# photodiodeAmplifier.net
KiCad netlist of a schematic drawn in Altium Designer
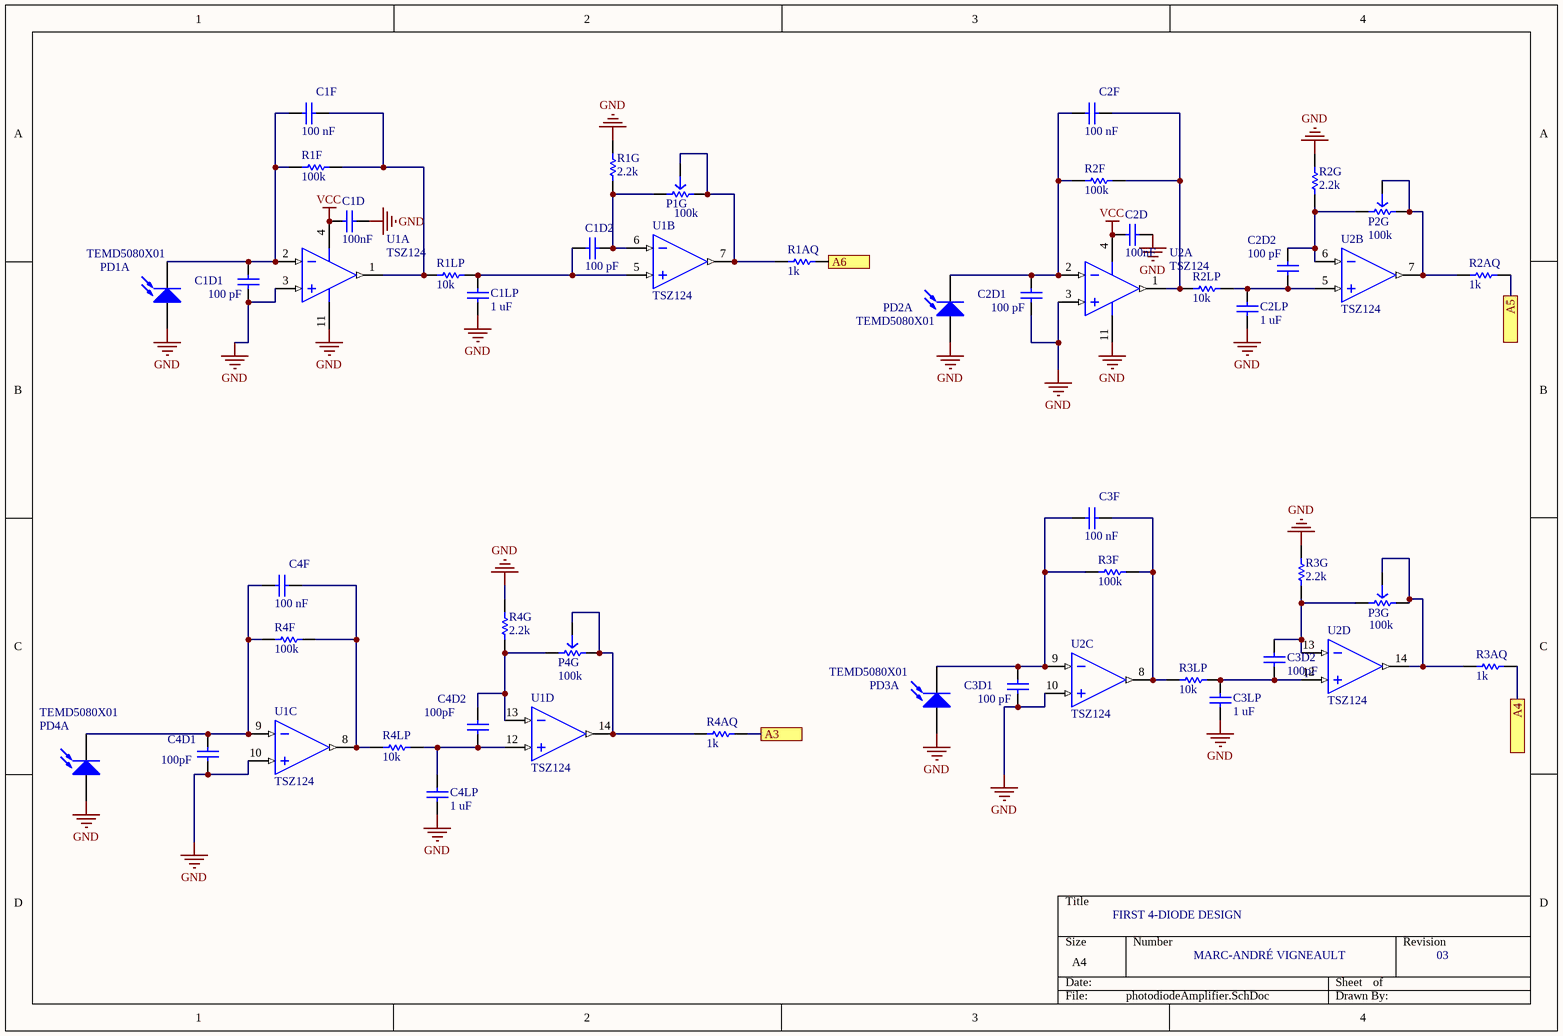
[diagram p0: photodiodeAmplifier.SchDoc]

(export (version "E")
  (design (tool "Eeschema 10.0.6"))
  (components
    (comp (ref "C1D") (value "100nF") (footprint "CAP 0805") (libsource (lib "AcqBoxLib") (part "CAP 0805")))
    (comp (ref "C1D1")
      (value "100 pF")
      (footprint "CAP 0805")
      (libsource (lib "AcqBoxLib") (part "CAP 0805"))
    )
    (comp (ref "C1D2")
      (value "100 pF")
      (footprint "CAP 0805")
      (libsource (lib "AcqBoxLib") (part "CAP 0805"))
    )
    (comp (ref "C1F") (value "100 nF") (footprint "CAP 0805") (libsource (lib "AcqBoxLib") (part "CAP 0805")))
    (comp (ref "C1LP") (value "1 uF") (footprint "CAP 0805") (libsource (lib "AcqBoxLib") (part "CAP 0805")))
    (comp (ref "C2D") (value "100nF") (footprint "CAP 0805") (libsource (lib "AcqBoxLib") (part "CAP 0805")))
    (comp (ref "C2D1")
      (value "100 pF")
      (footprint "CAP 0805")
      (libsource (lib "AcqBoxLib") (part "CAP 0805"))
    )
    (comp (ref "C2D2")
      (value "100 pF")
      (footprint "CAP 0805")
      (libsource (lib "AcqBoxLib") (part "CAP 0805"))
    )
    (comp (ref "C2F") (value "100 nF") (footprint "CAP 0805") (libsource (lib "AcqBoxLib") (part "CAP 0805")))
    (comp (ref "C2LP") (value "1 uF") (footprint "CAP 0805") (libsource (lib "AcqBoxLib") (part "CAP 0805")))
    (comp (ref "C3D1")
      (value "100 pF")
      (footprint "CAP 0805")
      (libsource (lib "AcqBoxLib") (part "CAP 0805"))
    )
    (comp (ref "C3D2") (value "100pF") (footprint "CAP 0805") (libsource (lib "AcqBoxLib") (part "CAP 0805")))
    (comp (ref "C3F") (value "100 nF") (footprint "CAP 0805") (libsource (lib "AcqBoxLib") (part "CAP 0805")))
    (comp (ref "C3LP") (value "1 uF") (footprint "CAP 0805") (libsource (lib "AcqBoxLib") (part "CAP 0805")))
    (comp (ref "C4D1") (value "100pF") (footprint "CAP 0805") (libsource (lib "AcqBoxLib") (part "CAP 0805")))
    (comp (ref "C4D2") (value "100pF") (footprint "CAP 0805") (libsource (lib "AcqBoxLib") (part "CAP 0805")))
    (comp (ref "C4F") (value "100 nF") (footprint "CAP 0805") (libsource (lib "AcqBoxLib") (part "CAP 0805")))
    (comp (ref "C4LP") (value "1 uF") (footprint "CAP 0805") (libsource (lib "AcqBoxLib") (part "CAP 0805")))
    (comp (ref "P1G")
      (value "100k")
      (footprint "potentiometer trimmer straight")
      (libsource (lib "AcqBoxLib") (part "Potentiometer Trimmer 90deg"))
    )
    (comp (ref "P2G")
      (value "100k")
      (footprint "potentiometer trimmer straight")
      (fields (field (name "Comment") "Potentiometer Trimmer 90deg"))
      (libsource (lib "AcqBoxLib") (part "Potentiometer Trimmer 90deg"))
    )
    (comp (ref "P3G")
      (value "100k")
      (footprint "potentiometer trimmer straight")
      (fields (field (name "Comment") "Potentiometer Trimmer 90deg"))
      (libsource (lib "AcqBoxLib") (part "Potentiometer Trimmer 90deg"))
    )
    (comp (ref "P4G")
      (value "100k")
      (footprint "potentiometer trimmer straight")
      (libsource (lib "AcqBoxLib") (part "Potentiometer Trimmer 90deg"))
    )
    (comp (ref "PD1")
      (value "TEMD5080X01")
      (footprint "Photodiode SMD PKG-1")
      (description "PIN Sillicium photodiode.")
      (libsource (lib "neigeMegaShieldLibrary") (part "TEMD5080X01"))
    )
    (comp (ref "PD2")
      (value "TEMD5080X01")
      (footprint "Photodiode SMD PKG-1")
      (description "PIN Sillicium photodiode.")
      (libsource (lib "neigeMegaShieldLibrary") (part "TEMD5080X01"))
    )
    (comp (ref "PD3")
      (value "TEMD5080X01")
      (footprint "Photodiode SMD PKG-1")
      (description "PIN Sillicium photodiode.")
      (libsource (lib "neigeMegaShieldLibrary") (part "TEMD5080X01"))
    )
    (comp (ref "PD4")
      (value "TEMD5080X01")
      (footprint "Photodiode SMD PKG-1")
      (description "PIN Sillicium photodiode.")
      (libsource (lib "neigeMegaShieldLibrary") (part "TEMD5080X01"))
    )
    (comp (ref "R1AQ")
      (value "1k")
      (footprint "RES 0805")
      (description "SMD Resistor 0805")
      (fields (field (name "Comment") "RES 0805"))
      (libsource (lib "AcqBoxLib") (part "RES 0805"))
    )
    (comp (ref "R1F")
      (value "100k")
      (footprint "RES 0805")
      (description "SMD Resistor 0805")
      (fields (field (name "Comment") "RES 0805"))
      (libsource (lib "AcqBoxLib") (part "RES 0805"))
    )
    (comp (ref "R1G")
      (value "2.2k")
      (footprint "RES 0805")
      (description "SMD Resistor 0805")
      (fields (field (name "Comment") "RES 0805"))
      (libsource (lib "AcqBoxLib") (part "RES 0805"))
    )
    (comp (ref "R1LP")
      (value "10k")
      (footprint "RES 0805")
      (description "SMD Resistor 0805")
      (fields (field (name "Comment") "RES 0805"))
      (libsource (lib "AcqBoxLib") (part "RES 0805"))
    )
    (comp (ref "R2AQ")
      (value "1k")
      (footprint "RES 0805")
      (description "SMD Resistor 0805")
      (fields (field (name "Comment") "RES 0805"))
      (libsource (lib "AcqBoxLib") (part "RES 0805"))
    )
    (comp (ref "R2F")
      (value "100k")
      (footprint "RES 0805")
      (description "SMD Resistor 0805")
      (fields (field (name "Comment") "RES 0805"))
      (libsource (lib "AcqBoxLib") (part "RES 0805"))
    )
    (comp (ref "R2G")
      (value "2.2k")
      (footprint "RES 0805")
      (description "SMD Resistor 0805")
      (fields (field (name "Comment") "RES 0805"))
      (libsource (lib "AcqBoxLib") (part "RES 0805"))
    )
    (comp (ref "R2LP")
      (value "10k")
      (footprint "RES 0805")
      (description "SMD Resistor 0805")
      (fields (field (name "Comment") "RES 0805"))
      (libsource (lib "AcqBoxLib") (part "RES 0805"))
    )
    (comp (ref "R3AQ")
      (value "1k")
      (footprint "RES 0805")
      (description "SMD Resistor 0805")
      (fields (field (name "Comment") "RES 0805"))
      (libsource (lib "AcqBoxLib") (part "RES 0805"))
    )
    (comp (ref "R3F")
      (value "100k")
      (footprint "RES 0805")
      (description "SMD Resistor 0805")
      (fields (field (name "Comment") "RES 0805"))
      (libsource (lib "AcqBoxLib") (part "RES 0805"))
    )
    (comp (ref "R3G")
      (value "2.2k")
      (footprint "RES 0805")
      (description "SMD Resistor 0805")
      (fields (field (name "Comment") "RES 0805"))
      (libsource (lib "AcqBoxLib") (part "RES 0805"))
    )
    (comp (ref "R3LP")
      (value "10k")
      (footprint "RES 0805")
      (description "SMD Resistor 0805")
      (fields (field (name "Comment") "RES 0805"))
      (libsource (lib "AcqBoxLib") (part "RES 0805"))
    )
    (comp (ref "R4AQ")
      (value "1k")
      (footprint "RES 0805")
      (description "SMD Resistor 0805")
      (fields (field (name "Comment") "RES 0805"))
      (libsource (lib "AcqBoxLib") (part "RES 0805"))
    )
    (comp (ref "R4F")
      (value "100k")
      (footprint "RES 0805")
      (description "SMD Resistor 0805")
      (fields (field (name "Comment") "RES 0805"))
      (libsource (lib "AcqBoxLib") (part "RES 0805"))
    )
    (comp (ref "R4G")
      (value "2.2k")
      (footprint "RES 0805")
      (description "SMD Resistor 0805")
      (fields (field (name "Comment") "RES 0805"))
      (libsource (lib "AcqBoxLib") (part "RES 0805"))
    )
    (comp (ref "R4LP")
      (value "10k")
      (footprint "RES 0805")
      (description "SMD Resistor 0805")
      (fields (field (name "Comment") "RES 0805"))
      (libsource (lib "AcqBoxLib") (part "RES 0805"))
    )
    (comp (ref "U1") (value "TSZ124") (footprint "TSSOP14") (libsource (lib "AcqBoxLib") (part "TSZ124")))
    (comp (ref "U2") (value "TSZ124") (footprint "TSSOP14") (libsource (lib "AcqBoxLib") (part "TSZ124")))
  )
  (nets
    (net (code "1") (name "/A3") (class "Default")
      (node (ref "R4AQ") (pin "2") (pinfunction "2_2") (pintype "passive"))
    )
    (net (code "2") (name "/A4") (class "Default")
      (node (ref "R3AQ") (pin "2") (pinfunction "2_2") (pintype "passive"))
    )
    (net (code "3") (name "/A5") (class "Default")
      (node (ref "R2AQ") (pin "2") (pinfunction "2_2") (pintype "passive"))
    )
    (net (code "4") (name "/A6") (class "Default")
      (node (ref "R1AQ") (pin "2") (pinfunction "2_2") (pintype "passive"))
    )
    (net (code "5") (name "GND") (class "Default")
      (node (ref "C1D") (pin "1") (pinfunction "1_1") (pintype "passive"))
      (node (ref "C1D1") (pin "1") (pinfunction "1_1") (pintype "passive"))
      (node (ref "C1LP") (pin "1") (pinfunction "1_1") (pintype "passive"))
      (node (ref "C2D") (pin "1") (pinfunction "1_1") (pintype "passive"))
      (node (ref "C2D1") (pin "1") (pinfunction "1_1") (pintype "passive"))
      (node (ref "C2LP") (pin "1") (pinfunction "1_1") (pintype "passive"))
      (node (ref "C3D1") (pin "1") (pinfunction "1_1") (pintype "passive"))
      (node (ref "C3LP") (pin "1") (pinfunction "1_1") (pintype "passive"))
      (node (ref "C4D1") (pin "1") (pinfunction "1_1") (pintype "passive"))
      (node (ref "C4LP") (pin "1") (pinfunction "1_1") (pintype "passive"))
      (node (ref "PD1") (pin "1") (pinfunction "1_1") (pintype "passive"))
      (node (ref "PD2") (pin "1") (pinfunction "1_1") (pintype "passive"))
      (node (ref "PD3") (pin "1") (pinfunction "1_1") (pintype "passive"))
      (node (ref "PD4") (pin "1") (pinfunction "1_1") (pintype "passive"))
      (node (ref "R1G") (pin "2") (pinfunction "2_2") (pintype "passive"))
      (node (ref "R2G") (pin "2") (pinfunction "2_2") (pintype "passive"))
      (node (ref "R3G") (pin "2") (pinfunction "2_2") (pintype "passive"))
      (node (ref "R4G") (pin "2") (pinfunction "2_2") (pintype "passive"))
      (node (ref "U1") (pin "10") (pinfunction "INA+_10") (pintype "input"))
      (node (ref "U1") (pin "11") (pinfunction "V-_11") (pintype "power_in"))
      (node (ref "U1") (pin "3") (pinfunction "INA+_3") (pintype "input"))
      (node (ref "U2") (pin "10") (pinfunction "INA+_10") (pintype "input"))
      (node (ref "U2") (pin "11") (pinfunction "V-_11") (pintype "power_in"))
      (node (ref "U2") (pin "3") (pinfunction "INA+_3") (pintype "input"))
    )
    (net (code "6") (name "Net-(C3D2-Pad2)") (class "Default")
      (node (ref "C3D2") (pin "2") (pinfunction "2_2") (pintype "passive"))
      (node (ref "P3G") (pin "3") (pinfunction "3_3") (pintype "passive"))
      (node (ref "R3G") (pin "1") (pinfunction "1_1") (pintype "passive"))
      (node (ref "U2") (pin "13") (pintype "input"))
    )
    (net (code "7") (name "Net-(C4D2-Pad2)") (class "Default")
      (node (ref "C4D2") (pin "2") (pinfunction "2_2") (pintype "passive"))
      (node (ref "P4G") (pin "3") (pinfunction "3_3") (pintype "passive"))
      (node (ref "R4G") (pin "1") (pinfunction "1_1") (pintype "passive"))
      (node (ref "U1") (pin "13") (pintype "input"))
    )
    (net (code "8") (name "Net-(U1A-INA-)") (class "Default")
      (node (ref "C1D1") (pin "2") (pinfunction "2_2") (pintype "passive"))
      (node (ref "C1F") (pin "1") (pinfunction "1_1") (pintype "passive"))
      (node (ref "PD1") (pin "2") (pinfunction "2_2") (pintype "passive"))
      (node (ref "R1F") (pin "1") (pinfunction "1_1") (pintype "passive"))
      (node (ref "U1") (pin "2") (pinfunction "INA-_2") (pintype "input"))
    )
    (net (code "9") (name "Net-(U1A-OUTA)") (class "Default")
      (node (ref "C1F") (pin "2") (pinfunction "2_2") (pintype "passive"))
      (node (ref "R1F") (pin "2") (pinfunction "2_2") (pintype "passive"))
      (node (ref "R1LP") (pin "1") (pinfunction "1_1") (pintype "passive"))
      (node (ref "U1") (pin "1") (pinfunction "OUTA_1") (pintype "output"))
    )
    (net (code "10") (name "Net-(U1B-INA+)") (class "Default")
      (node (ref "C1D2") (pin "1") (pinfunction "1_1") (pintype "passive"))
      (node (ref "C1LP") (pin "2") (pinfunction "2_2") (pintype "passive"))
      (node (ref "R1LP") (pin "2") (pinfunction "2_2") (pintype "passive"))
      (node (ref "U1") (pin "5") (pinfunction "INA+_5") (pintype "input"))
    )
    (net (code "11") (name "Net-(U1B-INA-)") (class "Default")
      (node (ref "C1D2") (pin "2") (pinfunction "2_2") (pintype "passive"))
      (node (ref "P1G") (pin "3") (pinfunction "3_3") (pintype "passive"))
      (node (ref "R1G") (pin "1") (pinfunction "1_1") (pintype "passive"))
      (node (ref "U1") (pin "6") (pinfunction "INA-_6") (pintype "input"))
    )
    (net (code "12") (name "Net-(U1B-OUTA)") (class "Default")
      (node (ref "P1G") (pin "1") (pinfunction "1_1") (pintype "passive"))
      (node (ref "P1G") (pin "2") (pinfunction "2_2") (pintype "passive"))
      (node (ref "R1AQ") (pin "1") (pinfunction "1_1") (pintype "passive"))
      (node (ref "U1") (pin "7") (pinfunction "OUTA_7") (pintype "output"))
    )
    (net (code "13") (name "Net-(U1C-INA-)") (class "Default")
      (node (ref "C4D1") (pin "2") (pinfunction "2_2") (pintype "passive"))
      (node (ref "C4F") (pin "1") (pinfunction "1_1") (pintype "passive"))
      (node (ref "PD4") (pin "2") (pinfunction "2_2") (pintype "passive"))
      (node (ref "R4F") (pin "1") (pinfunction "1_1") (pintype "passive"))
      (node (ref "U1") (pin "9") (pinfunction "INA-_9") (pintype "input"))
    )
    (net (code "14") (name "Net-(U1C-OUTA)") (class "Default")
      (node (ref "C4F") (pin "2") (pinfunction "2_2") (pintype "passive"))
      (node (ref "R4F") (pin "2") (pinfunction "2_2") (pintype "passive"))
      (node (ref "R4LP") (pin "1") (pinfunction "1_1") (pintype "passive"))
      (node (ref "U1") (pin "8") (pinfunction "OUTA_8") (pintype "output"))
    )
    (net (code "15") (name "Net-(U1D-INA+)") (class "Default")
      (node (ref "C4D2") (pin "1") (pinfunction "1_1") (pintype "passive"))
      (node (ref "C4LP") (pin "2") (pinfunction "2_2") (pintype "passive"))
      (node (ref "R4LP") (pin "2") (pinfunction "2_2") (pintype "passive"))
      (node (ref "U1") (pin "12") (pinfunction "INA+_12") (pintype "input"))
    )
    (net (code "16") (name "Net-(U1D-OUTA)") (class "Default")
      (node (ref "P4G") (pin "1") (pinfunction "1_1") (pintype "passive"))
      (node (ref "P4G") (pin "2") (pinfunction "2_2") (pintype "passive"))
      (node (ref "R4AQ") (pin "1") (pinfunction "1_1") (pintype "passive"))
      (node (ref "U1") (pin "14") (pinfunction "OUTA_14") (pintype "output"))
    )
    (net (code "17") (name "Net-(U2A-INA-)") (class "Default")
      (node (ref "C2D1") (pin "2") (pinfunction "2_2") (pintype "passive"))
      (node (ref "C2F") (pin "1") (pinfunction "1_1") (pintype "passive"))
      (node (ref "PD2") (pin "2") (pinfunction "2_2") (pintype "passive"))
      (node (ref "R2F") (pin "1") (pinfunction "1_1") (pintype "passive"))
      (node (ref "U2") (pin "2") (pinfunction "INA-_2") (pintype "input"))
    )
    (net (code "18") (name "Net-(U2A-OUTA)") (class "Default")
      (node (ref "C2F") (pin "2") (pinfunction "2_2") (pintype "passive"))
      (node (ref "R2F") (pin "2") (pinfunction "2_2") (pintype "passive"))
      (node (ref "R2LP") (pin "1") (pinfunction "1_1") (pintype "passive"))
      (node (ref "U2") (pin "1") (pinfunction "OUTA_1") (pintype "output"))
    )
    (net (code "19") (name "Net-(U2B-INA+)") (class "Default")
      (node (ref "C2D2") (pin "1") (pinfunction "1_1") (pintype "passive"))
      (node (ref "C2LP") (pin "2") (pinfunction "2_2") (pintype "passive"))
      (node (ref "R2LP") (pin "2") (pinfunction "2_2") (pintype "passive"))
      (node (ref "U2") (pin "5") (pinfunction "INA+_5") (pintype "input"))
    )
    (net (code "20") (name "Net-(U2B-INA-)") (class "Default")
      (node (ref "C2D2") (pin "2") (pinfunction "2_2") (pintype "passive"))
      (node (ref "P2G") (pin "3") (pinfunction "3_3") (pintype "passive"))
      (node (ref "R2G") (pin "1") (pinfunction "1_1") (pintype "passive"))
      (node (ref "U2") (pin "6") (pinfunction "INA-_6") (pintype "input"))
    )
    (net (code "21") (name "Net-(U2B-OUTA)") (class "Default")
      (node (ref "P2G") (pin "1") (pinfunction "1_1") (pintype "passive"))
      (node (ref "P2G") (pin "2") (pinfunction "2_2") (pintype "passive"))
      (node (ref "R2AQ") (pin "1") (pinfunction "1_1") (pintype "passive"))
      (node (ref "U2") (pin "7") (pinfunction "OUTA_7") (pintype "output"))
    )
    (net (code "22") (name "Net-(U2C-INA-)") (class "Default")
      (node (ref "C3D1") (pin "2") (pinfunction "2_2") (pintype "passive"))
      (node (ref "C3F") (pin "1") (pinfunction "1_1") (pintype "passive"))
      (node (ref "PD3") (pin "2") (pinfunction "2_2") (pintype "passive"))
      (node (ref "R3F") (pin "1") (pinfunction "1_1") (pintype "passive"))
      (node (ref "U2") (pin "9") (pinfunction "INA-_9") (pintype "input"))
    )
    (net (code "23") (name "Net-(U2C-OUTA)") (class "Default")
      (node (ref "C3F") (pin "2") (pinfunction "2_2") (pintype "passive"))
      (node (ref "R3F") (pin "2") (pinfunction "2_2") (pintype "passive"))
      (node (ref "R3LP") (pin "1") (pinfunction "1_1") (pintype "passive"))
      (node (ref "U2") (pin "8") (pinfunction "OUTA_8") (pintype "output"))
    )
    (net (code "24") (name "Net-(U2D-INA+)") (class "Default")
      (node (ref "C3D2") (pin "1") (pinfunction "1_1") (pintype "passive"))
      (node (ref "C3LP") (pin "2") (pinfunction "2_2") (pintype "passive"))
      (node (ref "R3LP") (pin "2") (pinfunction "2_2") (pintype "passive"))
      (node (ref "U2") (pin "12") (pinfunction "INA+_12") (pintype "input"))
    )
    (net (code "25") (name "Net-(U2D-OUTA)") (class "Default")
      (node (ref "P3G") (pin "1") (pinfunction "1_1") (pintype "passive"))
      (node (ref "P3G") (pin "2") (pinfunction "2_2") (pintype "passive"))
      (node (ref "R3AQ") (pin "1") (pinfunction "1_1") (pintype "passive"))
      (node (ref "U2") (pin "14") (pinfunction "OUTA_14") (pintype "output"))
    )
    (net (code "26") (name "VCC") (class "Default")
      (node (ref "C1D") (pin "2") (pinfunction "2_2") (pintype "passive"))
      (node (ref "C2D") (pin "2") (pinfunction "2_2") (pintype "passive"))
      (node (ref "U1") (pin "4") (pinfunction "V+_4") (pintype "power_in"))
      (node (ref "U2") (pin "4") (pinfunction "V+_4") (pintype "power_in"))
    )
  )
)
